# fngAfro.net
KiCad netlist of a schematic drawn in EAGLE
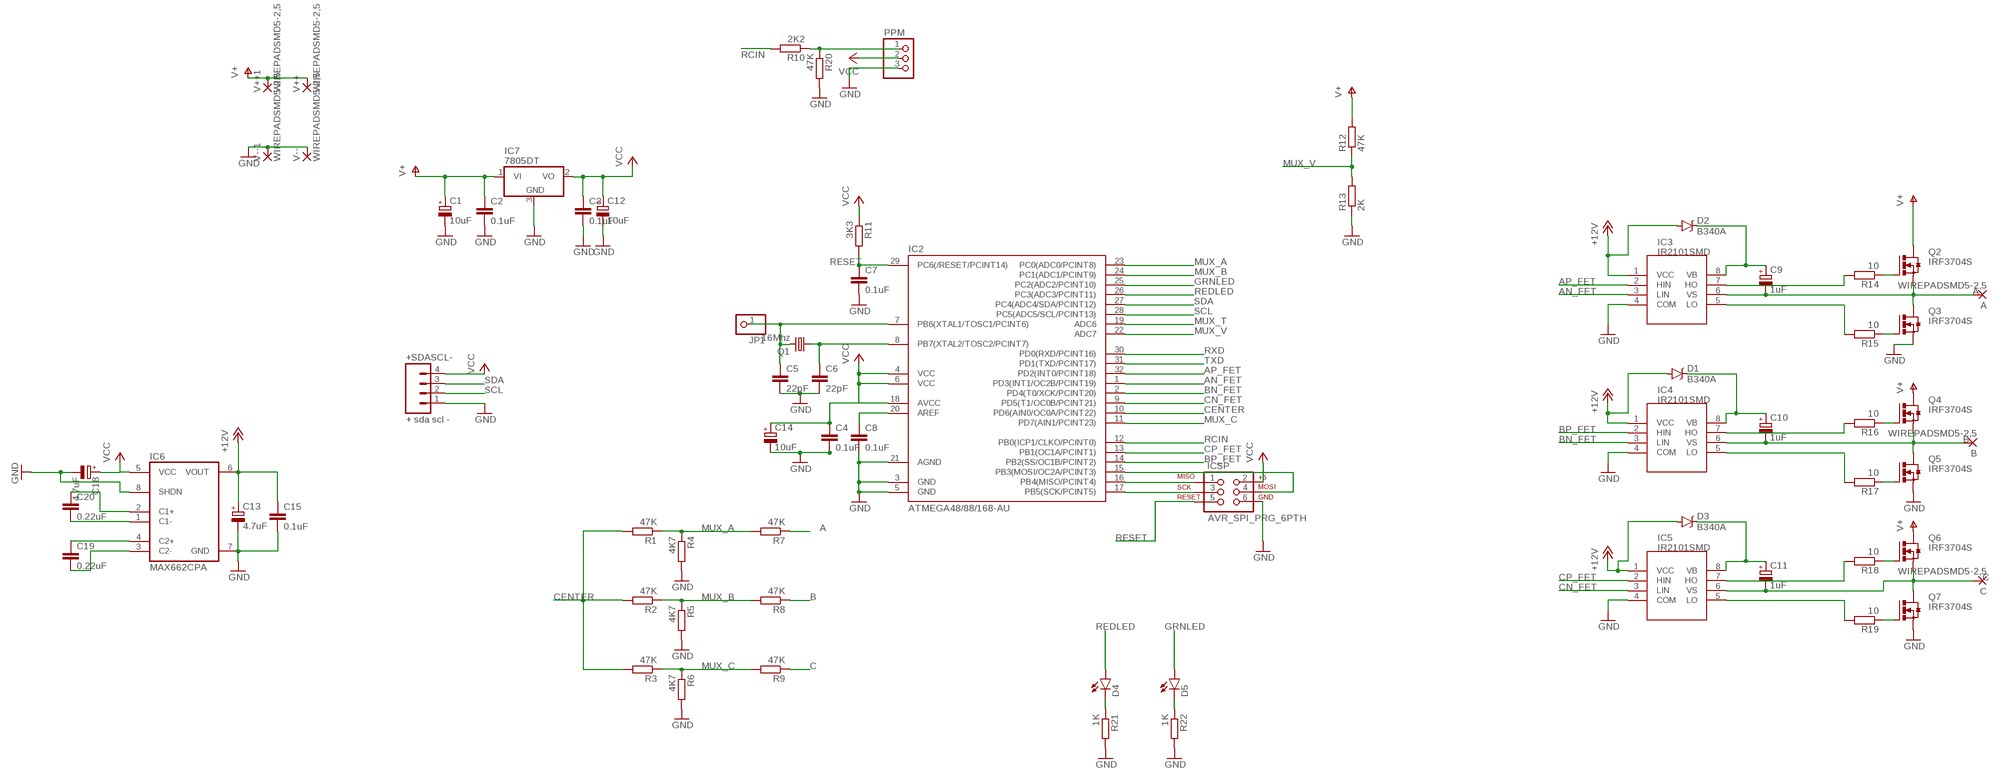
[diagram p0: schematic, sheet 1]

(export (version "E")
  (design (tool "Eeschema 10.0.6"))
  (components
    (comp (ref "+SDASCL-")
      (value "+ sda scl -")
      (footprint "eagle-import:1X04_LOCK")
      (libsource (lib "eagle-import") (part "M04LOCK"))
    )
    (comp (ref "A")
      (value "WIREPADSMD5-2,5")
      (footprint "eagle-import:5-2,5")
      (libsource (lib "eagle-import") (part "WIREPADSMD5-2,5"))
    )
    (comp (ref "B")
      (value "WIREPADSMD5-2,5")
      (footprint "eagle-import:5-2,5")
      (libsource (lib "eagle-import") (part "WIREPADSMD5-2,5"))
    )
    (comp (ref "C")
      (value "WIREPADSMD5-2,5")
      (footprint "eagle-import:5-2,5")
      (libsource (lib "eagle-import") (part "WIREPADSMD5-2,5"))
    )
    (comp (ref "C1")
      (value "10uF")
      (footprint "eagle-import:CT3216")
      (libsource (lib "eagle-import") (part "CPOL-EUCT3216"))
    )
    (comp (ref "C2")
      (value "0.1uF")
      (footprint "eagle-import:C1206K")
      (libsource (lib "eagle-import") (part "C-EUC1206K"))
    )
    (comp (ref "C3")
      (value "0.1uF")
      (footprint "eagle-import:C1206K")
      (libsource (lib "eagle-import") (part "C-EUC1206K"))
    )
    (comp (ref "C4")
      (value "0.1uF")
      (footprint "eagle-import:C1206K")
      (libsource (lib "eagle-import") (part "C-EUC1206K"))
    )
    (comp (ref "C5")
      (value "22pF")
      (footprint "eagle-import:C1206K")
      (libsource (lib "eagle-import") (part "C-EUC1206K"))
    )
    (comp (ref "C6")
      (value "22pF")
      (footprint "eagle-import:C1206K")
      (libsource (lib "eagle-import") (part "C-EUC1206K"))
    )
    (comp (ref "C7")
      (value "0.1uF")
      (footprint "eagle-import:C1206K")
      (libsource (lib "eagle-import") (part "C-EUC1206K"))
    )
    (comp (ref "C8")
      (value "0.1uF")
      (footprint "eagle-import:C1206K")
      (libsource (lib "eagle-import") (part "C-EUC1206K"))
    )
    (comp (ref "C9")
      (value "1uF")
      (footprint "eagle-import:B_3528-21R")
      (libsource (lib "eagle-import") (part "CPOL-EUB/3528-21R"))
    )
    (comp (ref "C10")
      (value "1uF")
      (footprint "eagle-import:B_3528-21R")
      (libsource (lib "eagle-import") (part "CPOL-EUB/3528-21R"))
    )
    (comp (ref "C11")
      (value "1uF")
      (footprint "eagle-import:B_3528-21R")
      (libsource (lib "eagle-import") (part "CPOL-EUB/3528-21R"))
    )
    (comp (ref "C12")
      (value "10uF")
      (footprint "eagle-import:A_3216-18W")
      (libsource (lib "eagle-import") (part "CPOL-EUA/3216-18W"))
    )
    (comp (ref "C13")
      (value "4.7uF")
      (footprint "eagle-import:CT3216")
      (libsource (lib "eagle-import") (part "CPOL-EUCT3216"))
    )
    (comp (ref "C14")
      (value "10uF")
      (footprint "eagle-import:A_3216-18W")
      (libsource (lib "eagle-import") (part "CPOL-EUA/3216-18W"))
    )
    (comp (ref "C15")
      (value "0.1uF")
      (footprint "eagle-import:C1206K")
      (libsource (lib "eagle-import") (part "C-EUC1206K"))
    )
    (comp (ref "C18")
      (value "4.7uF")
      (footprint "eagle-import:CT3216")
      (libsource (lib "eagle-import") (part "CPOL-EUCT3216"))
    )
    (comp (ref "C19")
      (value "0.22uF")
      (footprint "eagle-import:C1206K")
      (libsource (lib "eagle-import") (part "C-EUC1206K"))
    )
    (comp (ref "C20")
      (value "0.22uF")
      (footprint "eagle-import:C1206K")
      (libsource (lib "eagle-import") (part "C-EUC1206K"))
    )
    (comp (ref "D1")
      (value "B340A")
      (footprint "eagle-import:SMA-DIODE")
      (libsource (lib "eagle-import") (part "DIODE-SCHOTTKY-B340A"))
    )
    (comp (ref "D2")
      (value "B340A")
      (footprint "eagle-import:SMA-DIODE")
      (libsource (lib "eagle-import") (part "DIODE-SCHOTTKY-B340A"))
    )
    (comp (ref "D3")
      (value "B340A")
      (footprint "eagle-import:SMA-DIODE")
      (libsource (lib "eagle-import") (part "DIODE-SCHOTTKY-B340A"))
    )
    (comp (ref "D4")
      (value "LED-FKIT-1206")
      (footprint "eagle-import:FKIT-LED-1206")
      (libsource (lib "eagle-import") (part "LED-FKIT-1206"))
    )
    (comp (ref "D5")
      (value "LED-FKIT-1206")
      (footprint "eagle-import:FKIT-LED-1206")
      (libsource (lib "eagle-import") (part "LED-FKIT-1206"))
    )
    (comp (ref "IC2")
      (value "ATMEGA48/88/168-AU")
      (footprint "eagle-import:TQFP32-08")
      (libsource (lib "eagle-import") (part "ATMEGA48/88/168-AU"))
    )
    (comp (ref "IC3")
      (value "IR2101SMD")
      (footprint "eagle-import:SO08")
      (libsource (lib "eagle-import") (part "IR2101SMD"))
    )
    (comp (ref "IC4")
      (value "IR2101SMD")
      (footprint "eagle-import:SO08")
      (libsource (lib "eagle-import") (part "IR2101SMD"))
    )
    (comp (ref "IC5")
      (value "IR2101SMD")
      (footprint "eagle-import:SO08")
      (libsource (lib "eagle-import") (part "IR2101SMD"))
    )
    (comp (ref "IC6")
      (value "MAX662CPA")
      (footprint "eagle-import:SO08")
      (libsource (lib "eagle-import") (part "MAX662CPA"))
    )
    (comp (ref "IC7")
      (value "7805DT")
      (footprint "eagle-import:TO252")
      (libsource (lib "eagle-import") (part "78DT05"))
    )
    (comp (ref "ICSP")
      (value "AVR_SPI_PRG_6PTH")
      (footprint "eagle-import:2X3")
      (libsource (lib "eagle-import") (part "AVR_SPI_PRG_6PTH"))
    )
    (comp (ref "JP1")
      (value "PINHD-1X1")
      (footprint "eagle-import:1X01")
      (libsource (lib "eagle-import") (part "PINHD-1X1"))
    )
    (comp (ref "PPM")
      (value "PINHD-1X3")
      (footprint "eagle-import:1X03")
      (libsource (lib "eagle-import") (part "PINHD-1X3"))
    )
    (comp (ref "Q1")
      (value "16Mhz")
      (footprint "eagle-import:HC49U70")
      (libsource (lib "eagle-import") (part "CRYSTALHC49U70"))
    )
    (comp (ref "Q2")
      (value "IRF3704S")
      (footprint "eagle-import:D2PACK")
      (libsource (lib "eagle-import") (part "IRF3704S"))
    )
    (comp (ref "Q3")
      (value "IRF3704S")
      (footprint "eagle-import:D2PACK")
      (libsource (lib "eagle-import") (part "IRF3704S"))
    )
    (comp (ref "Q4")
      (value "IRF3704S")
      (footprint "eagle-import:D2PACK")
      (libsource (lib "eagle-import") (part "IRF3704S"))
    )
    (comp (ref "Q5")
      (value "IRF3704S")
      (footprint "eagle-import:D2PACK")
      (libsource (lib "eagle-import") (part "IRF3704S"))
    )
    (comp (ref "Q6")
      (value "IRF3704S")
      (footprint "eagle-import:D2PACK")
      (libsource (lib "eagle-import") (part "IRF3704S"))
    )
    (comp (ref "Q7")
      (value "IRF3704S")
      (footprint "eagle-import:D2PACK")
      (libsource (lib "eagle-import") (part "IRF3704S"))
    )
    (comp (ref "R1")
      (value "47K")
      (footprint "eagle-import:M0805")
      (libsource (lib "eagle-import") (part "R-EU_M0805"))
    )
    (comp (ref "R2")
      (value "47K")
      (footprint "eagle-import:M0805")
      (libsource (lib "eagle-import") (part "R-EU_M0805"))
    )
    (comp (ref "R3")
      (value "47K")
      (footprint "eagle-import:M0805")
      (libsource (lib "eagle-import") (part "R-EU_M0805"))
    )
    (comp (ref "R4")
      (value "4K7")
      (footprint "eagle-import:M0805")
      (libsource (lib "eagle-import") (part "R-EU_M0805"))
    )
    (comp (ref "R5")
      (value "4K7")
      (footprint "eagle-import:M0805")
      (libsource (lib "eagle-import") (part "R-EU_M0805"))
    )
    (comp (ref "R6")
      (value "4K7")
      (footprint "eagle-import:M0805")
      (libsource (lib "eagle-import") (part "R-EU_M0805"))
    )
    (comp (ref "R7")
      (value "47K")
      (footprint "eagle-import:M0805")
      (libsource (lib "eagle-import") (part "R-EU_M0805"))
    )
    (comp (ref "R8")
      (value "47K")
      (footprint "eagle-import:M0805")
      (libsource (lib "eagle-import") (part "R-EU_M0805"))
    )
    (comp (ref "R9")
      (value "47K")
      (footprint "eagle-import:M0805")
      (libsource (lib "eagle-import") (part "R-EU_M0805"))
    )
    (comp (ref "R10")
      (value "2K2")
      (footprint "eagle-import:M1206")
      (libsource (lib "eagle-import") (part "R-EU_M1206"))
    )
    (comp (ref "R11")
      (value "3K3")
      (footprint "eagle-import:M1206")
      (libsource (lib "eagle-import") (part "R-EU_M1206"))
    )
    (comp (ref "R12")
      (value "47K")
      (footprint "eagle-import:M0805")
      (libsource (lib "eagle-import") (part "R-EU_M0805"))
    )
    (comp (ref "R13")
      (value "2K")
      (footprint "eagle-import:M0805")
      (libsource (lib "eagle-import") (part "R-EU_M0805"))
    )
    (comp (ref "R14")
      (value "10")
      (footprint "eagle-import:M0805")
      (libsource (lib "eagle-import") (part "R-EU_M0805"))
    )
    (comp (ref "R15")
      (value "10")
      (footprint "eagle-import:M0805")
      (libsource (lib "eagle-import") (part "R-EU_M0805"))
    )
    (comp (ref "R16")
      (value "10")
      (footprint "eagle-import:M0805")
      (libsource (lib "eagle-import") (part "R-EU_M0805"))
    )
    (comp (ref "R17")
      (value "10")
      (footprint "eagle-import:M0805")
      (libsource (lib "eagle-import") (part "R-EU_M0805"))
    )
    (comp (ref "R18")
      (value "10")
      (footprint "eagle-import:M0805")
      (libsource (lib "eagle-import") (part "R-EU_M0805"))
    )
    (comp (ref "R19")
      (value "10")
      (footprint "eagle-import:M0805")
      (libsource (lib "eagle-import") (part "R-EU_M0805"))
    )
    (comp (ref "R20")
      (value "47K")
      (footprint "eagle-import:M1206")
      (libsource (lib "eagle-import") (part "R-EU_M1206"))
    )
    (comp (ref "R21")
      (value "1K")
      (footprint "eagle-import:M0805")
      (libsource (lib "eagle-import") (part "R-EU_M0805"))
    )
    (comp (ref "R22")
      (value "1K")
      (footprint "eagle-import:M0805")
      (libsource (lib "eagle-import") (part "R-EU_M0805"))
    )
    (comp (ref "V++")
      (value "WIREPADSMD5-2,5")
      (footprint "eagle-import:5-2,5")
      (libsource (lib "eagle-import") (part "WIREPADSMD5-2,5"))
    )
    (comp (ref "V++1")
      (value "WIREPADSMD5-2,5")
      (footprint "eagle-import:5-2,5")
      (libsource (lib "eagle-import") (part "WIREPADSMD5-2,5"))
    )
    (comp (ref "V--")
      (value "WIREPADSMD5-2,5")
      (footprint "eagle-import:5-2,5")
      (libsource (lib "eagle-import") (part "WIREPADSMD5-2,5"))
    )
    (comp (ref "V--1")
      (value "WIREPADSMD5-2,5")
      (footprint "eagle-import:5-2,5")
      (libsource (lib "eagle-import") (part "WIREPADSMD5-2,5"))
    )
  )
  (nets
    (net (code "1") (name "+12V") (class "Default")
      (node (ref "C13") (pin "+") (pinfunction "+_+") (pintype "passive"))
      (node (ref "C15") (pin "1") (pinfunction "1_1") (pintype "passive"))
      (node (ref "D1") (pin "A") (pinfunction "A_A") (pintype "passive"))
      (node (ref "D2") (pin "A") (pinfunction "A_A") (pintype "passive"))
      (node (ref "D3") (pin "A") (pinfunction "A_A") (pintype "passive"))
      (node (ref "IC3") (pin "1") (pinfunction "VCC_1") (pintype "bidirectional"))
      (node (ref "IC4") (pin "1") (pinfunction "VCC_1") (pintype "bidirectional"))
      (node (ref "IC5") (pin "1") (pinfunction "VCC_1") (pintype "bidirectional"))
      (node (ref "IC6") (pin "6") (pinfunction "VOUT_6") (pintype "power_in"))
    )
    (net (code "2") (name "/A") (class "Default")
      (node (ref "A") (pin "1") (pinfunction "P_1") (pintype "passive"))
      (node (ref "C9") (pin "-") (pinfunction "-_-") (pintype "passive"))
      (node (ref "IC3") (pin "6") (pinfunction "VS_6") (pintype "bidirectional"))
      (node (ref "Q2") (pin "3") (pinfunction "S_3") (pintype "passive"))
      (node (ref "Q3") (pin "2") (pinfunction "D_2") (pintype "passive"))
      (node (ref "R7") (pin "1") (pinfunction "1_1") (pintype "passive"))
    )
    (net (code "3") (name "/AN_FET") (class "Default")
      (node (ref "IC2") (pin "1") (pinfunction "PD3(INT1/OC2B/PCINT19)_1") (pintype "bidirectional"))
      (node (ref "IC3") (pin "3") (pinfunction "LIN_3") (pintype "bidirectional"))
    )
    (net (code "4") (name "/AP_FET") (class "Default")
      (node (ref "IC2") (pin "32") (pinfunction "PD2(INT0/PCINT18)_32") (pintype "bidirectional"))
      (node (ref "IC3") (pin "2") (pinfunction "HIN_2") (pintype "bidirectional"))
    )
    (net (code "5") (name "/B") (class "Default")
      (node (ref "B") (pin "1") (pinfunction "P_1") (pintype "passive"))
      (node (ref "C10") (pin "-") (pinfunction "-_-") (pintype "passive"))
      (node (ref "IC4") (pin "6") (pinfunction "VS_6") (pintype "bidirectional"))
      (node (ref "Q4") (pin "3") (pinfunction "S_3") (pintype "passive"))
      (node (ref "Q5") (pin "2") (pinfunction "D_2") (pintype "passive"))
      (node (ref "R8") (pin "1") (pinfunction "1_1") (pintype "passive"))
    )
    (net (code "6") (name "/BN_FET") (class "Default")
      (node (ref "IC2") (pin "2") (pinfunction "PD4(T0/XCK/PCINT20)_2") (pintype "bidirectional"))
      (node (ref "IC4") (pin "3") (pinfunction "LIN_3") (pintype "bidirectional"))
    )
    (net (code "7") (name "/BP_FET") (class "Default")
      (node (ref "IC2") (pin "14") (pinfunction "PB2(SS/OC1B/PCINT2)_14") (pintype "bidirectional"))
      (node (ref "IC4") (pin "2") (pinfunction "HIN_2") (pintype "bidirectional"))
    )
    (net (code "8") (name "/C") (class "Default")
      (node (ref "C") (pin "1") (pinfunction "P_1") (pintype "passive"))
      (node (ref "C11") (pin "-") (pinfunction "-_-") (pintype "passive"))
      (node (ref "IC5") (pin "6") (pinfunction "VS_6") (pintype "bidirectional"))
      (node (ref "Q6") (pin "3") (pinfunction "S_3") (pintype "passive"))
      (node (ref "Q7") (pin "2") (pinfunction "D_2") (pintype "passive"))
      (node (ref "R9") (pin "1") (pinfunction "1_1") (pintype "passive"))
    )
    (net (code "9") (name "/CENTER") (class "Default")
      (node (ref "IC2") (pin "10") (pinfunction "PD6(AIN0/OC0A/PCINT22)_10") (pintype "bidirectional"))
      (node (ref "R1") (pin "2") (pinfunction "2_2") (pintype "passive"))
      (node (ref "R2") (pin "2") (pinfunction "2_2") (pintype "passive"))
      (node (ref "R3") (pin "2") (pinfunction "2_2") (pintype "passive"))
    )
    (net (code "10") (name "/CN_FET") (class "Default")
      (node (ref "IC2") (pin "9") (pinfunction "PD5(T1/OC0B/PCINT21)_9") (pintype "bidirectional"))
      (node (ref "IC5") (pin "3") (pinfunction "LIN_3") (pintype "bidirectional"))
    )
    (net (code "11") (name "/CP_FET") (class "Default")
      (node (ref "IC2") (pin "13") (pinfunction "PB1(OC1A/PCINT1)_13") (pintype "bidirectional"))
      (node (ref "IC5") (pin "2") (pinfunction "HIN_2") (pintype "bidirectional"))
    )
    (net (code "12") (name "/GRNLED") (class "Default")
      (node (ref "D5") (pin "A") (pinfunction "A_A") (pintype "passive"))
      (node (ref "IC2") (pin "25") (pinfunction "PC2(ADC2/PCINT10)_25") (pintype "bidirectional"))
    )
    (net (code "13") (name "/MUX_A") (class "Default")
      (node (ref "IC2") (pin "23") (pinfunction "PC0(ADC0/PCINT8)_23") (pintype "bidirectional"))
      (node (ref "R1") (pin "1") (pinfunction "1_1") (pintype "passive"))
      (node (ref "R4") (pin "1") (pinfunction "1_1") (pintype "passive"))
      (node (ref "R7") (pin "2") (pinfunction "2_2") (pintype "passive"))
    )
    (net (code "14") (name "/MUX_B") (class "Default")
      (node (ref "IC2") (pin "24") (pinfunction "PC1(ADC1/PCINT9)_24") (pintype "bidirectional"))
      (node (ref "R2") (pin "1") (pinfunction "1_1") (pintype "passive"))
      (node (ref "R5") (pin "1") (pinfunction "1_1") (pintype "passive"))
      (node (ref "R8") (pin "2") (pinfunction "2_2") (pintype "passive"))
    )
    (net (code "15") (name "/MUX_C") (class "Default")
      (node (ref "IC2") (pin "11") (pinfunction "PD7(AIN1/PCINT23)_11") (pintype "bidirectional"))
      (node (ref "R3") (pin "1") (pinfunction "1_1") (pintype "passive"))
      (node (ref "R6") (pin "1") (pinfunction "1_1") (pintype "passive"))
      (node (ref "R9") (pin "2") (pinfunction "2_2") (pintype "passive"))
    )
    (net (code "16") (name "/MUX_T") (class "Default")
      (node (ref "IC2") (pin "19") (pinfunction "ADC6_19") (pintype "passive"))
    )
    (net (code "17") (name "/MUX_V") (class "Default")
      (node (ref "IC2") (pin "22") (pinfunction "ADC7_22") (pintype "passive"))
      (node (ref "R12") (pin "1") (pinfunction "1_1") (pintype "passive"))
      (node (ref "R13") (pin "2") (pinfunction "2_2") (pintype "passive"))
    )
    (net (code "18") (name "/RCIN") (class "Default")
      (node (ref "IC2") (pin "12") (pinfunction "PB0(ICP1/CLKO/PCINT0)_12") (pintype "bidirectional"))
      (node (ref "R10") (pin "2") (pinfunction "2_2") (pintype "passive"))
    )
    (net (code "19") (name "/REDLED") (class "Default")
      (node (ref "D4") (pin "A") (pinfunction "A_A") (pintype "passive"))
      (node (ref "IC2") (pin "26") (pinfunction "PC3(ADC3/PCINT11)_26") (pintype "bidirectional"))
    )
    (net (code "20") (name "/RESET") (class "Default")
      (node (ref "C7") (pin "1") (pinfunction "1_1") (pintype "passive"))
      (node (ref "IC2") (pin "29") (pinfunction "PC6(/RESET/PCINT14)_29") (pintype "bidirectional"))
      (node (ref "ICSP") (pin "5") (pinfunction "5_5") (pintype "passive"))
      (node (ref "R11") (pin "2") (pinfunction "2_2") (pintype "passive"))
    )
    (net (code "21") (name "/RXD") (class "Default")
      (node (ref "IC2") (pin "30") (pinfunction "PD0(RXD/PCINT16)_30") (pintype "bidirectional"))
    )
    (net (code "22") (name "/SCL") (class "Default")
      (node (ref "+SDASCL-") (pin "2") (pinfunction "2_2") (pintype "passive"))
      (node (ref "IC2") (pin "28") (pinfunction "PC5(ADC5/SCL/PCINT13)_28") (pintype "bidirectional"))
    )
    (net (code "23") (name "/SDA") (class "Default")
      (node (ref "+SDASCL-") (pin "3") (pinfunction "3_3") (pintype "passive"))
      (node (ref "IC2") (pin "27") (pinfunction "PC4(ADC4/SDA/PCINT12)_27") (pintype "bidirectional"))
    )
    (net (code "24") (name "/TXD") (class "Default")
      (node (ref "IC2") (pin "31") (pinfunction "PD1(TXD/PCINT17)_31") (pintype "bidirectional"))
    )
    (net (code "25") (name "GND") (class "Default")
      (node (ref "+SDASCL-") (pin "1") (pinfunction "1_1") (pintype "passive"))
      (node (ref "C1") (pin "-") (pinfunction "-_-") (pintype "passive"))
      (node (ref "C12") (pin "-") (pinfunction "-_-") (pintype "passive"))
      (node (ref "C13") (pin "-") (pinfunction "-_-") (pintype "passive"))
      (node (ref "C14") (pin "-") (pinfunction "-_-") (pintype "passive"))
      (node (ref "C15") (pin "2") (pinfunction "2_2") (pintype "passive"))
      (node (ref "C18") (pin "-") (pinfunction "-_-") (pintype "passive"))
      (node (ref "C2") (pin "2") (pinfunction "2_2") (pintype "passive"))
      (node (ref "C3") (pin "2") (pinfunction "2_2") (pintype "passive"))
      (node (ref "C4") (pin "2") (pinfunction "2_2") (pintype "passive"))
      (node (ref "C5") (pin "2") (pinfunction "2_2") (pintype "passive"))
      (node (ref "C6") (pin "2") (pinfunction "2_2") (pintype "passive"))
      (node (ref "C7") (pin "2") (pinfunction "2_2") (pintype "passive"))
      (node (ref "C8") (pin "2") (pinfunction "2_2") (pintype "passive"))
      (node (ref "IC2") (pin "21") (pinfunction "AGND_21") (pintype "power_in"))
      (node (ref "IC2") (pin "3") (pinfunction "GND_3") (pintype "power_in"))
      (node (ref "IC2") (pin "5") (pinfunction "GND_5") (pintype "power_in"))
      (node (ref "IC3") (pin "4") (pinfunction "COM_4") (pintype "bidirectional"))
      (node (ref "IC4") (pin "4") (pinfunction "COM_4") (pintype "bidirectional"))
      (node (ref "IC5") (pin "4") (pinfunction "COM_4") (pintype "bidirectional"))
      (node (ref "IC6") (pin "7") (pinfunction "GND_7") (pintype "power_in"))
      (node (ref "IC6") (pin "8") (pinfunction "SHDN_8") (pintype "input"))
      (node (ref "IC7") (pin "3") (pinfunction "GND_3") (pintype "passive"))
      (node (ref "ICSP") (pin "6") (pinfunction "6_6") (pintype "passive"))
      (node (ref "PPM") (pin "3") (pinfunction "3_3") (pintype "passive"))
      (node (ref "Q3") (pin "3") (pinfunction "S_3") (pintype "passive"))
      (node (ref "Q5") (pin "3") (pinfunction "S_3") (pintype "passive"))
      (node (ref "Q7") (pin "3") (pinfunction "S_3") (pintype "passive"))
      (node (ref "R13") (pin "1") (pinfunction "1_1") (pintype "passive"))
      (node (ref "R20") (pin "2") (pinfunction "2_2") (pintype "passive"))
      (node (ref "R21") (pin "2") (pinfunction "2_2") (pintype "passive"))
      (node (ref "R22") (pin "2") (pinfunction "2_2") (pintype "passive"))
      (node (ref "R4") (pin "2") (pinfunction "2_2") (pintype "passive"))
      (node (ref "R5") (pin "2") (pinfunction "2_2") (pintype "passive"))
      (node (ref "R6") (pin "2") (pinfunction "2_2") (pintype "passive"))
      (node (ref "V--") (pin "1") (pinfunction "P_1") (pintype "passive"))
      (node (ref "V--1") (pin "1") (pinfunction "P_1") (pintype "passive"))
    )
    (net (code "26") (name "Net-(D4-PadC)") (class "Default")
      (node (ref "D4") (pin "C") (pinfunction "C_C") (pintype "passive"))
      (node (ref "R21") (pin "1") (pinfunction "1_1") (pintype "passive"))
    )
    (net (code "27") (name "Net-(D5-PadC)") (class "Default")
      (node (ref "D5") (pin "C") (pinfunction "C_C") (pintype "passive"))
      (node (ref "R22") (pin "1") (pinfunction "1_1") (pintype "passive"))
    )
    (net (code "28") (name "Net-(IC2-AREF)") (class "Default")
      (node (ref "C8") (pin "1") (pinfunction "1_1") (pintype "passive"))
      (node (ref "IC2") (pin "20") (pinfunction "AREF_20") (pintype "passive"))
    )
    (net (code "29") (name "Net-(IC2-PB3(MOSI{slash}OC2A{slash}PCINT3))") (class "Default")
      (node (ref "IC2") (pin "15") (pinfunction "PB3(MOSI/OC2A/PCINT3)_15") (pintype "bidirectional"))
      (node (ref "ICSP") (pin "4") (pinfunction "4_4") (pintype "passive"))
    )
    (net (code "30") (name "Net-(IC2-PB4(MISO{slash}PCINT4))") (class "Default")
      (node (ref "IC2") (pin "16") (pinfunction "PB4(MISO/PCINT4)_16") (pintype "bidirectional"))
      (node (ref "ICSP") (pin "1") (pinfunction "1_1") (pintype "passive"))
    )
    (net (code "31") (name "Net-(IC2-PB5(SCK{slash}PCINT5))") (class "Default")
      (node (ref "IC2") (pin "17") (pinfunction "PB5(SCK/PCINT5)_17") (pintype "bidirectional"))
      (node (ref "ICSP") (pin "3") (pinfunction "3_3") (pintype "passive"))
    )
    (net (code "32") (name "Net-(IC2-PB6(XTAL1{slash}TOSC1{slash}PCINT6))") (class "Default")
      (node (ref "C5") (pin "1") (pinfunction "1_1") (pintype "passive"))
      (node (ref "IC2") (pin "7") (pinfunction "PB6(XTAL1/TOSC1/PCINT6)_7") (pintype "bidirectional"))
      (node (ref "JP1") (pin "1") (pinfunction "1_1") (pintype "passive"))
      (node (ref "Q1") (pin "2") (pinfunction "2_2") (pintype "passive"))
    )
    (net (code "33") (name "Net-(IC2-PB7(XTAL2{slash}TOSC2{slash}PCINT7))") (class "Default")
      (node (ref "C6") (pin "1") (pinfunction "1_1") (pintype "passive"))
      (node (ref "IC2") (pin "8") (pinfunction "PB7(XTAL2/TOSC2/PCINT7)_8") (pintype "bidirectional"))
      (node (ref "Q1") (pin "1") (pinfunction "1_1") (pintype "passive"))
    )
    (net (code "34") (name "Net-(IC3-HO)") (class "Default")
      (node (ref "IC3") (pin "7") (pinfunction "HO_7") (pintype "bidirectional"))
      (node (ref "R14") (pin "2") (pinfunction "2_2") (pintype "passive"))
    )
    (net (code "35") (name "Net-(IC3-LO)") (class "Default")
      (node (ref "IC3") (pin "5") (pinfunction "LO_5") (pintype "bidirectional"))
      (node (ref "R15") (pin "2") (pinfunction "2_2") (pintype "passive"))
    )
    (net (code "36") (name "Net-(IC3-VB)") (class "Default")
      (node (ref "C9") (pin "+") (pinfunction "+_+") (pintype "passive"))
      (node (ref "D2") (pin "C") (pinfunction "C_C") (pintype "passive"))
      (node (ref "IC3") (pin "8") (pinfunction "VB_8") (pintype "bidirectional"))
    )
    (net (code "37") (name "Net-(IC4-HO)") (class "Default")
      (node (ref "IC4") (pin "7") (pinfunction "HO_7") (pintype "bidirectional"))
      (node (ref "R16") (pin "2") (pinfunction "2_2") (pintype "passive"))
    )
    (net (code "38") (name "Net-(IC4-LO)") (class "Default")
      (node (ref "IC4") (pin "5") (pinfunction "LO_5") (pintype "bidirectional"))
      (node (ref "R17") (pin "2") (pinfunction "2_2") (pintype "passive"))
    )
    (net (code "39") (name "Net-(IC4-VB)") (class "Default")
      (node (ref "C10") (pin "+") (pinfunction "+_+") (pintype "passive"))
      (node (ref "D1") (pin "C") (pinfunction "C_C") (pintype "passive"))
      (node (ref "IC4") (pin "8") (pinfunction "VB_8") (pintype "bidirectional"))
    )
    (net (code "40") (name "Net-(IC5-HO)") (class "Default")
      (node (ref "IC5") (pin "7") (pinfunction "HO_7") (pintype "bidirectional"))
      (node (ref "R18") (pin "2") (pinfunction "2_2") (pintype "passive"))
    )
    (net (code "41") (name "Net-(IC5-LO)") (class "Default")
      (node (ref "IC5") (pin "5") (pinfunction "LO_5") (pintype "bidirectional"))
      (node (ref "R19") (pin "2") (pinfunction "2_2") (pintype "passive"))
    )
    (net (code "42") (name "Net-(IC5-VB)") (class "Default")
      (node (ref "C11") (pin "+") (pinfunction "+_+") (pintype "passive"))
      (node (ref "D3") (pin "C") (pinfunction "C_C") (pintype "passive"))
      (node (ref "IC5") (pin "8") (pinfunction "VB_8") (pintype "bidirectional"))
    )
    (net (code "43") (name "Net-(IC6-C1+)") (class "Default")
      (node (ref "C20") (pin "1") (pinfunction "1_1") (pintype "passive"))
      (node (ref "IC6") (pin "2") (pinfunction "C1+_2") (pintype "passive"))
    )
    (net (code "44") (name "Net-(IC6-C1-)") (class "Default")
      (node (ref "C20") (pin "2") (pinfunction "2_2") (pintype "passive"))
      (node (ref "IC6") (pin "1") (pinfunction "C1-_1") (pintype "passive"))
    )
    (net (code "45") (name "Net-(IC6-C2+)") (class "Default")
      (node (ref "C19") (pin "1") (pinfunction "1_1") (pintype "passive"))
      (node (ref "IC6") (pin "4") (pinfunction "C2+_4") (pintype "passive"))
    )
    (net (code "46") (name "Net-(IC6-C2-)") (class "Default")
      (node (ref "C19") (pin "2") (pinfunction "2_2") (pintype "passive"))
      (node (ref "IC6") (pin "3") (pinfunction "C2-_3") (pintype "passive"))
    )
    (net (code "47") (name "Net-(PPM-Pad1)") (class "Default")
      (node (ref "PPM") (pin "1") (pinfunction "1_1") (pintype "passive"))
      (node (ref "R10") (pin "1") (pinfunction "1_1") (pintype "passive"))
      (node (ref "R20") (pin "1") (pinfunction "1_1") (pintype "passive"))
    )
    (net (code "48") (name "Net-(Q2-G)") (class "Default")
      (node (ref "Q2") (pin "1") (pinfunction "G_1") (pintype "passive"))
      (node (ref "R14") (pin "1") (pinfunction "1_1") (pintype "passive"))
    )
    (net (code "49") (name "Net-(Q3-G)") (class "Default")
      (node (ref "Q3") (pin "1") (pinfunction "G_1") (pintype "passive"))
      (node (ref "R15") (pin "1") (pinfunction "1_1") (pintype "passive"))
    )
    (net (code "50") (name "Net-(Q4-G)") (class "Default")
      (node (ref "Q4") (pin "1") (pinfunction "G_1") (pintype "passive"))
      (node (ref "R16") (pin "1") (pinfunction "1_1") (pintype "passive"))
    )
    (net (code "51") (name "Net-(Q5-G)") (class "Default")
      (node (ref "Q5") (pin "1") (pinfunction "G_1") (pintype "passive"))
      (node (ref "R17") (pin "1") (pinfunction "1_1") (pintype "passive"))
    )
    (net (code "52") (name "Net-(Q6-G)") (class "Default")
      (node (ref "Q6") (pin "1") (pinfunction "G_1") (pintype "passive"))
      (node (ref "R18") (pin "1") (pinfunction "1_1") (pintype "passive"))
    )
    (net (code "53") (name "Net-(Q7-G)") (class "Default")
      (node (ref "Q7") (pin "1") (pinfunction "G_1") (pintype "passive"))
      (node (ref "R19") (pin "1") (pinfunction "1_1") (pintype "passive"))
    )
    (net (code "54") (name "V+") (class "Default")
      (node (ref "C1") (pin "+") (pinfunction "+_+") (pintype "passive"))
      (node (ref "C2") (pin "1") (pinfunction "1_1") (pintype "passive"))
      (node (ref "IC7") (pin "1") (pinfunction "VI_1") (pintype "input"))
      (node (ref "Q2") (pin "2") (pinfunction "D_2") (pintype "passive"))
      (node (ref "Q4") (pin "2") (pinfunction "D_2") (pintype "passive"))
      (node (ref "Q6") (pin "2") (pinfunction "D_2") (pintype "passive"))
      (node (ref "R12") (pin "2") (pinfunction "2_2") (pintype "passive"))
      (node (ref "V++") (pin "1") (pinfunction "P_1") (pintype "passive"))
      (node (ref "V++1") (pin "1") (pinfunction "P_1") (pintype "passive"))
    )
    (net (code "55") (name "VCC") (class "Default")
      (node (ref "+SDASCL-") (pin "4") (pinfunction "4_4") (pintype "passive"))
      (node (ref "C12") (pin "+") (pinfunction "+_+") (pintype "passive"))
      (node (ref "C14") (pin "+") (pinfunction "+_+") (pintype "passive"))
      (node (ref "C18") (pin "+") (pinfunction "+_+") (pintype "passive"))
      (node (ref "C3") (pin "1") (pinfunction "1_1") (pintype "passive"))
      (node (ref "C4") (pin "1") (pinfunction "1_1") (pintype "passive"))
      (node (ref "IC2") (pin "18") (pinfunction "AVCC_18") (pintype "passive"))
      (node (ref "IC2") (pin "4") (pinfunction "VCC_4") (pintype "power_in"))
      (node (ref "IC2") (pin "6") (pinfunction "VCC_6") (pintype "power_in"))
      (node (ref "IC6") (pin "5") (pinfunction "VCC_5") (pintype "power_in"))
      (node (ref "IC7") (pin "2") (pinfunction "VO_2") (pintype "passive"))
      (node (ref "ICSP") (pin "2") (pinfunction "2_2") (pintype "passive"))
      (node (ref "PPM") (pin "2") (pinfunction "2_2") (pintype "passive"))
      (node (ref "R11") (pin "1") (pinfunction "1_1") (pintype "passive"))
    )
  )
)
